# open-lux-A.net
KiCad netlist of a schematic drawn in EAGLE
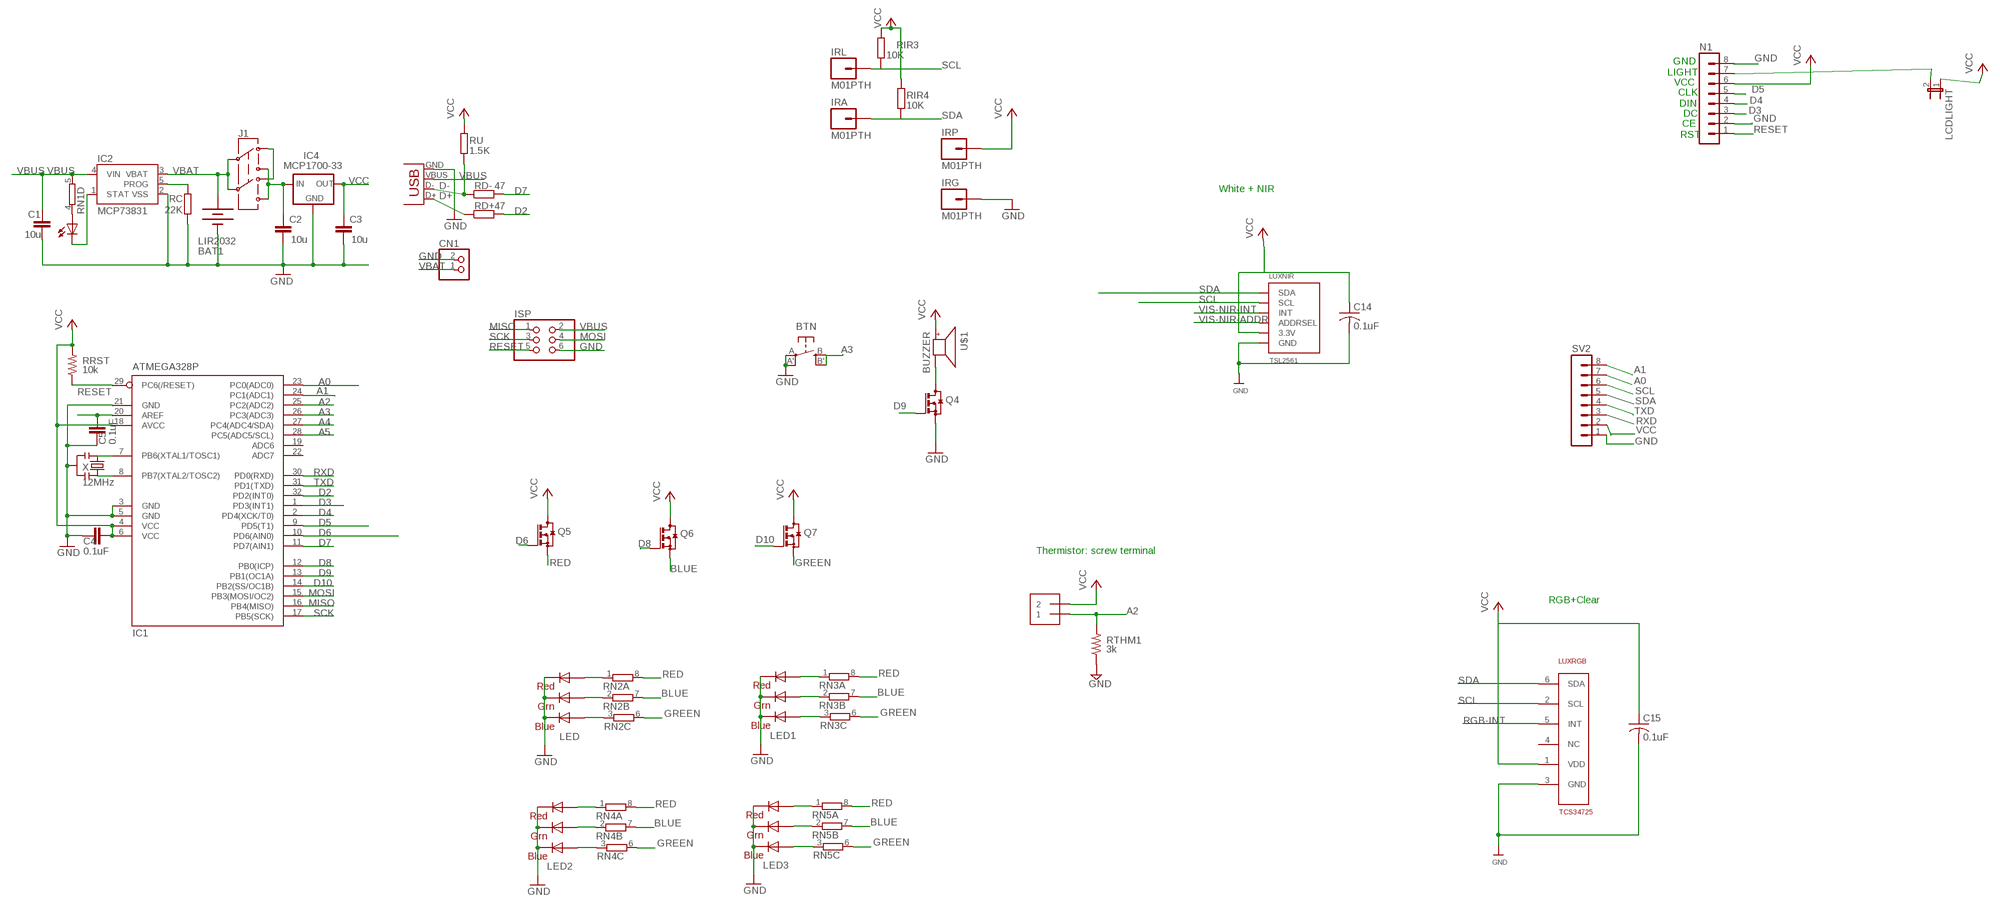
[diagram p0: schematic, sheet 1]

(export (version "E")
  (design (tool "Eeschema 10.0.6"))
  (components
    (comp (ref "BAT1")
      (value "LIR2032")
      (footprint "eagle-import:BATTCOM_20MM_PTH_SMT")
      (libsource (lib "eagle-import") (part "BATTERYBATTCOM_20MM_PTH_SMT"))
    )
    (comp (ref "BTN")
      (value "EVQQ2")
      (footprint "eagle-import:EVQ-Q2")
      (libsource (lib "eagle-import") (part "EVQQ2"))
    )
    (comp (ref "C1")
      (value "10u")
      (footprint "eagle-import:C0805")
      (libsource (lib "eagle-import") (part "resistor_C-EUC0805"))
    )
    (comp (ref "C2")
      (value "10u")
      (footprint "eagle-import:C0805")
      (libsource (lib "eagle-import") (part "resistor_C-EUC0805"))
    )
    (comp (ref "C3")
      (value "10u")
      (footprint "eagle-import:C0805")
      (libsource (lib "eagle-import") (part "resistor_C-EUC0805"))
    )
    (comp (ref "C4")
      (value "0.1uF")
      (footprint "eagle-import:C0805")
      (libsource (lib "eagle-import") (part "C-EUC0805"))
    )
    (comp (ref "C5")
      (value "0.1uF")
      (footprint "eagle-import:C0805")
      (libsource (lib "eagle-import") (part "C-EUC0805"))
    )
    (comp (ref "C14")
      (value "0.1uF")
      (footprint "eagle-import:C0805")
      (libsource (lib "eagle-import") (part "C-USC0805"))
    )
    (comp (ref "C15")
      (value "0.1uF")
      (footprint "eagle-import:C0805")
      (libsource (lib "eagle-import") (part "C-USC0805"))
    )
    (comp (ref "CHG")
      (value "0805")
      (footprint "eagle-import:CHIPLED_0805")
      (libsource (lib "eagle-import") (part "LEDCHIPLED_0805"))
    )
    (comp (ref "CN1")
      (value "JST_2PIN-SMT-RA")
      (footprint "eagle-import:JST-PH-2-SMT-RA")
      (libsource (lib "eagle-import") (part "JST_2PIN-SMT-RA"))
    )
    (comp (ref "IC1")
      (value "ATMEGA328P")
      (footprint "eagle-import:TQFP32-08")
      (fields (field (name "MPN") "ATMEGA8-16AU"))
      (libsource (lib "eagle-import") (part "MEGA8-AI"))
    )
    (comp (ref "IC2")
      (value "MCP73831")
      (footprint "eagle-import:SOT23-5")
      (libsource (lib "eagle-import") (part "MCP73831"))
    )
    (comp (ref "IC4")
      (value "MCP1700-33")
      (footprint "eagle-import:SOT23")
      (libsource (lib "eagle-import") (part "MCP1700SOT233"))
    )
    (comp (ref "IRA")
      (value "M01PTH")
      (footprint "eagle-import:1X01")
      (libsource (lib "eagle-import") (part "M01PTH"))
    )
    (comp (ref "IRG")
      (value "M01PTH")
      (footprint "eagle-import:1X01")
      (libsource (lib "eagle-import") (part "M01PTH"))
    )
    (comp (ref "IRL")
      (value "M01PTH")
      (footprint "eagle-import:1X01")
      (libsource (lib "eagle-import") (part "M01PTH"))
    )
    (comp (ref "IRP")
      (value "M01PTH")
      (footprint "eagle-import:1X01")
      (libsource (lib "eagle-import") (part "M01PTH"))
    )
    (comp (ref "ISP")
      (value "PINHD-2X3")
      (footprint "eagle-import:2X03")
      (libsource (lib "eagle-import") (part "PINHD-2X3"))
    )
    (comp (ref "J1")
      (value "AYZ0202")
      (footprint "eagle-import:AYZ0202")
      (libsource (lib "eagle-import") (part "AYZ0202"))
    )
    (comp (ref "LCDLIGHT")
      (value "JP1E")
      (footprint "eagle-import:JP1")
      (libsource (lib "eagle-import") (part "JP1E"))
    )
    (comp (ref "LED")
      (value "RGBLED5050")
      (footprint "eagle-import:RGBLED5050")
      (libsource (lib "eagle-import") (part "RGBLED5050"))
    )
    (comp (ref "LED1")
      (value "RGBLED5050")
      (footprint "eagle-import:RGBLED5050")
      (libsource (lib "eagle-import") (part "RGBLED5050"))
    )
    (comp (ref "LED2")
      (value "RGBLED5050")
      (footprint "eagle-import:RGBLED5050")
      (libsource (lib "eagle-import") (part "RGBLED5050"))
    )
    (comp (ref "LED3")
      (value "RGBLED5050")
      (footprint "eagle-import:RGBLED5050")
      (libsource (lib "eagle-import") (part "RGBLED5050"))
    )
    (comp (ref "LUXNIR")
      (value "TSL2561")
      (footprint "eagle-import:TSL2561_FN@1")
      (libsource (lib "eagle-import") (part "TSL2561"))
    )
    (comp (ref "LUXRGB")
      (value "TCS34725")
      (footprint "eagle-import:DFN-6")
      (libsource (lib "eagle-import") (part "TCS34725"))
    )
    (comp (ref "N1")
      (value "MA08-1")
      (footprint "eagle-import:MA08-1")
      (libsource (lib "eagle-import") (part "MA08-1"))
    )
    (comp (ref "Q4")
      (value "BSS123")
      (footprint "eagle-import:SOT23")
      (libsource (lib "eagle-import") (part "BSS123"))
    )
    (comp (ref "Q5")
      (value "BSS123")
      (footprint "eagle-import:SOT23")
      (libsource (lib "eagle-import") (part "BSS123"))
    )
    (comp (ref "Q6")
      (value "BSS123")
      (footprint "eagle-import:SOT23")
      (libsource (lib "eagle-import") (part "BSS123"))
    )
    (comp (ref "Q7")
      (value "BSS123")
      (footprint "eagle-import:SOT23")
      (libsource (lib "eagle-import") (part "BSS123"))
    )
    (comp (ref "RC")
      (value "22K")
      (footprint "eagle-import:R0805")
      (libsource (lib "eagle-import") (part "R-EU_R0805"))
    )
    (comp (ref "RD+")
      (value "47")
      (footprint "eagle-import:R0805")
      (libsource (lib "eagle-import") (part "R-EU_R0805"))
    )
    (comp (ref "RD-")
      (value "47")
      (footprint "eagle-import:R0805")
      (libsource (lib "eagle-import") (part "R-EU_R0805"))
    )
    (comp (ref "RIR3")
      (value "10K")
      (footprint "eagle-import:R0805")
      (libsource (lib "eagle-import") (part "R-EU_R0805"))
    )
    (comp (ref "RIR4")
      (value "10K")
      (footprint "eagle-import:R0805")
      (libsource (lib "eagle-import") (part "R-EU_R0805"))
    )
    (comp (ref "RN1")
      (value "4R-NEXB38V")
      (footprint "eagle-import:EXB38V")
      (libsource (lib "eagle-import") (part "4R-NEXB38V"))
    )
    (comp (ref "RN2")
      (value "4R-NEXB38V")
      (footprint "eagle-import:EXB38V")
      (libsource (lib "eagle-import") (part "4R-NEXB38V"))
    )
    (comp (ref "RN3")
      (value "4R-NEXB38V")
      (footprint "eagle-import:EXB38V")
      (libsource (lib "eagle-import") (part "4R-NEXB38V"))
    )
    (comp (ref "RN4")
      (value "4R-NEXB38V")
      (footprint "eagle-import:EXB38V")
      (libsource (lib "eagle-import") (part "4R-NEXB38V"))
    )
    (comp (ref "RN5")
      (value "4R-NEXB38V")
      (footprint "eagle-import:EXB38V")
      (libsource (lib "eagle-import") (part "4R-NEXB38V"))
    )
    (comp (ref "RRST")
      (value "10k")
      (footprint "eagle-import:R0805@1")
      (libsource (lib "eagle-import") (part "R-US_R0805"))
    )
    (comp (ref "RTHM1")
      (value "3k")
      (footprint "eagle-import:R0805@1")
      (libsource (lib "eagle-import") (part "R-US_R0805"))
    )
    (comp (ref "RU")
      (value "1.5K")
      (footprint "eagle-import:R0805")
      (libsource (lib "eagle-import") (part "R-EU_R0805"))
    )
    (comp (ref "SV2")
      (value "MA08-1")
      (footprint "eagle-import:MA08-1")
      (libsource (lib "eagle-import") (part "MA08-1"))
    )
    (comp (ref "THM1")
      (value "1X2-3.5MM")
      (footprint "eagle-import:1X2-3.5MM")
      (libsource (lib "eagle-import") (part "1X2-3.5MM"))
    )
    (comp (ref "U$1")
      (value "BUZZER")
      (footprint "eagle-import:SMT-8585-BUZZER")
      (libsource (lib "eagle-import") (part "BUZZER"))
    )
    (comp (ref "X")
      (value "12MHz")
      (footprint "eagle-import:RESONATOR-SMD")
      (libsource (lib "eagle-import") (part "RESONATORSMD"))
    )
    (comp (ref "X1")
      (value "USBSMD")
      (footprint "eagle-import:USB-MINIB")
      (libsource (lib "eagle-import") (part "USBSMD"))
    )
  )
  (nets
    (net (code "1") (name "/A0") (class "Default")
      (node (ref "IC1") (pin "23") (pinfunction "PC0(ADC0)_23") (pintype "bidirectional"))
      (node (ref "SV2") (pin "7") (pinfunction "7_7") (pintype "passive"))
    )
    (net (code "2") (name "/A1") (class "Default")
      (node (ref "IC1") (pin "24") (pinfunction "PC1(ADC1)_24") (pintype "bidirectional"))
      (node (ref "SV2") (pin "8") (pinfunction "8_8") (pintype "passive"))
    )
    (net (code "3") (name "/A2") (class "Default")
      (node (ref "IC1") (pin "25") (pinfunction "PC2(ADC2)_25") (pintype "bidirectional"))
      (node (ref "RTHM1") (pin "2") (pinfunction "2_2") (pintype "passive"))
      (node (ref "THM1") (pin "1") (pinfunction "1_1") (pintype "passive"))
    )
    (net (code "4") (name "/A3") (class "Default")
      (node (ref "BTN") (pin "B") (pinfunction "S_B") (pintype "passive"))
      (node (ref "BTN") (pin "B'") (pinfunction "S1_B'") (pintype "passive"))
      (node (ref "IC1") (pin "26") (pinfunction "PC3(ADC3)_26") (pintype "bidirectional"))
    )
    (net (code "5") (name "/A4") (class "Default")
      (node (ref "IC1") (pin "27") (pinfunction "PC4(ADC4/SDA)_27") (pintype "bidirectional"))
    )
    (net (code "6") (name "/A5") (class "Default")
      (node (ref "IC1") (pin "28") (pinfunction "PC5(ADC5/SCL)_28") (pintype "bidirectional"))
    )
    (net (code "7") (name "/BLUE") (class "Default")
      (node (ref "Q6") (pin "2") (pinfunction "S_2") (pintype "passive"))
      (node (ref "RN2") (pin "7") (pinfunction "2_7") (pintype "passive"))
      (node (ref "RN3") (pin "7") (pinfunction "2_7") (pintype "passive"))
      (node (ref "RN4") (pin "7") (pinfunction "2_7") (pintype "passive"))
      (node (ref "RN5") (pin "7") (pinfunction "2_7") (pintype "passive"))
    )
    (net (code "8") (name "/D+") (class "Default")
      (node (ref "RD+") (pin "1") (pinfunction "1_1") (pintype "passive"))
      (node (ref "X1") (pin "D+") (pinfunction "D+_D+") (pintype "bidirectional"))
    )
    (net (code "9") (name "/D-") (class "Default")
      (node (ref "RD-") (pin "1") (pinfunction "1_1") (pintype "passive"))
      (node (ref "RU") (pin "1") (pinfunction "1_1") (pintype "passive"))
      (node (ref "X1") (pin "D-") (pinfunction "D-_D-") (pintype "bidirectional"))
    )
    (net (code "10") (name "/D2") (class "Default")
      (node (ref "IC1") (pin "32") (pinfunction "PD2(INT0)_32") (pintype "bidirectional"))
      (node (ref "RD+") (pin "2") (pinfunction "2_2") (pintype "passive"))
    )
    (net (code "11") (name "/D3") (class "Default")
      (node (ref "IC1") (pin "1") (pinfunction "PD3(INT1)_1") (pintype "bidirectional"))
      (node (ref "N1") (pin "3") (pinfunction "3_3") (pintype "passive"))
    )
    (net (code "12") (name "/D4") (class "Default")
      (node (ref "IC1") (pin "2") (pinfunction "PD4(XCK/T0)_2") (pintype "bidirectional"))
      (node (ref "N1") (pin "4") (pinfunction "4_4") (pintype "passive"))
    )
    (net (code "13") (name "/D5") (class "Default")
      (node (ref "IC1") (pin "9") (pinfunction "PD5(T1)_9") (pintype "bidirectional"))
      (node (ref "N1") (pin "5") (pinfunction "5_5") (pintype "passive"))
    )
    (net (code "14") (name "/D6") (class "Default")
      (node (ref "IC1") (pin "10") (pinfunction "PD6(AIN0)_10") (pintype "bidirectional"))
      (node (ref "Q5") (pin "1") (pinfunction "G_1") (pintype "passive"))
    )
    (net (code "15") (name "/D7") (class "Default")
      (node (ref "IC1") (pin "11") (pinfunction "PD7(AIN1)_11") (pintype "bidirectional"))
      (node (ref "RD-") (pin "2") (pinfunction "2_2") (pintype "passive"))
    )
    (net (code "16") (name "/D8") (class "Default")
      (node (ref "IC1") (pin "12") (pinfunction "PB0(ICP)_12") (pintype "bidirectional"))
      (node (ref "Q6") (pin "1") (pinfunction "G_1") (pintype "passive"))
    )
    (net (code "17") (name "/D9") (class "Default")
      (node (ref "IC1") (pin "13") (pinfunction "PB1(OC1A)_13") (pintype "bidirectional"))
      (node (ref "Q4") (pin "1") (pinfunction "G_1") (pintype "passive"))
    )
    (net (code "18") (name "/D10") (class "Default")
      (node (ref "IC1") (pin "14") (pinfunction "PB2(SS/OC1B)_14") (pintype "bidirectional"))
      (node (ref "Q7") (pin "1") (pinfunction "G_1") (pintype "passive"))
    )
    (net (code "19") (name "/GREEN") (class "Default")
      (node (ref "Q7") (pin "2") (pinfunction "S_2") (pintype "passive"))
      (node (ref "RN2") (pin "6") (pinfunction "2_6") (pintype "passive"))
      (node (ref "RN3") (pin "6") (pinfunction "2_6") (pintype "passive"))
      (node (ref "RN4") (pin "6") (pinfunction "2_6") (pintype "passive"))
      (node (ref "RN5") (pin "6") (pinfunction "2_6") (pintype "passive"))
    )
    (net (code "20") (name "/MISO") (class "Default")
      (node (ref "IC1") (pin "16") (pinfunction "PB4(MISO)_16") (pintype "bidirectional"))
      (node (ref "ISP") (pin "1") (pinfunction "1_1") (pintype "passive"))
    )
    (net (code "21") (name "/MOSI") (class "Default")
      (node (ref "IC1") (pin "15") (pinfunction "PB3(MOSI/OC2)_15") (pintype "bidirectional"))
      (node (ref "ISP") (pin "4") (pinfunction "4_4") (pintype "passive"))
    )
    (net (code "22") (name "/RED") (class "Default")
      (node (ref "Q5") (pin "2") (pinfunction "S_2") (pintype "passive"))
      (node (ref "RN2") (pin "8") (pinfunction "2_8") (pintype "passive"))
      (node (ref "RN3") (pin "8") (pinfunction "2_8") (pintype "passive"))
      (node (ref "RN4") (pin "8") (pinfunction "2_8") (pintype "passive"))
      (node (ref "RN5") (pin "8") (pinfunction "2_8") (pintype "passive"))
    )
    (net (code "23") (name "/RESET") (class "Default")
      (node (ref "IC1") (pin "29") (pinfunction "PC6(/RESET)_29") (pintype "bidirectional"))
      (node (ref "ISP") (pin "5") (pinfunction "5_5") (pintype "passive"))
      (node (ref "N1") (pin "1") (pinfunction "1_1") (pintype "passive"))
      (node (ref "RRST") (pin "1") (pinfunction "1_1") (pintype "passive"))
    )
    (net (code "24") (name "/RGB-INT") (class "Default")
      (node (ref "LUXRGB") (pin "5") (pinfunction "INT_5") (pintype "bidirectional"))
    )
    (net (code "25") (name "/RXD") (class "Default")
      (node (ref "IC1") (pin "30") (pinfunction "PD0(RXD)_30") (pintype "bidirectional"))
      (node (ref "SV2") (pin "3") (pinfunction "3_3") (pintype "passive"))
    )
    (net (code "26") (name "/SCK") (class "Default")
      (node (ref "IC1") (pin "17") (pinfunction "PB5(SCK)_17") (pintype "bidirectional"))
      (node (ref "ISP") (pin "3") (pinfunction "3_3") (pintype "passive"))
    )
    (net (code "27") (name "/SCL") (class "Default")
      (node (ref "IRL") (pin "1") (pinfunction "1_1") (pintype "passive"))
      (node (ref "LUXNIR") (pin "CLK") (pinfunction "SCL_CLK") (pintype "bidirectional"))
      (node (ref "LUXRGB") (pin "2") (pinfunction "SCL_2") (pintype "bidirectional"))
      (node (ref "RIR3") (pin "1") (pinfunction "1_1") (pintype "passive"))
      (node (ref "SV2") (pin "6") (pinfunction "6_6") (pintype "passive"))
    )
    (net (code "28") (name "/SDA") (class "Default")
      (node (ref "IRA") (pin "1") (pinfunction "1_1") (pintype "passive"))
      (node (ref "LUXNIR") (pin "DATA") (pinfunction "SDA_DATA") (pintype "bidirectional"))
      (node (ref "LUXRGB") (pin "6") (pinfunction "SDA_6") (pintype "bidirectional"))
      (node (ref "RIR4") (pin "1") (pinfunction "1_1") (pintype "passive"))
      (node (ref "SV2") (pin "5") (pinfunction "5_5") (pintype "passive"))
    )
    (net (code "29") (name "/TXD") (class "Default")
      (node (ref "IC1") (pin "31") (pinfunction "PD1(TXD)_31") (pintype "bidirectional"))
      (node (ref "SV2") (pin "4") (pinfunction "4_4") (pintype "passive"))
    )
    (net (code "30") (name "/VBAT") (class "Default")
      (node (ref "BAT1") (pin "P$2") (pinfunction "+_P$2") (pintype "power_in"))
      (node (ref "CN1") (pin "1") (pinfunction "2_1") (pintype "passive"))
      (node (ref "IC2") (pin "3") (pinfunction "VBAT_3") (pintype "power_in"))
      (node (ref "J1") (pin "2") (pinfunction "2_2") (pintype "bidirectional"))
      (node (ref "J1") (pin "5") (pinfunction "5_5") (pintype "bidirectional"))
    )
    (net (code "31") (name "/VBUS") (class "Default")
      (node (ref "C1") (pin "1") (pinfunction "1_1") (pintype "passive"))
      (node (ref "IC2") (pin "4") (pinfunction "VIN_4") (pintype "power_in"))
      (node (ref "ISP") (pin "2") (pinfunction "2_2") (pintype "passive"))
      (node (ref "RN1") (pin "5") (pinfunction "2_5") (pintype "passive"))
      (node (ref "X1") (pin "VBUS") (pinfunction "VBUS_VBUS") (pintype "bidirectional"))
    )
    (net (code "32") (name "/VIS-NIR-ADDR") (class "Default")
      (node (ref "LUXNIR") (pin "ADR") (pinfunction "ADDRSEL_ADR") (pintype "bidirectional"))
    )
    (net (code "33") (name "/VIS-NIR-INT") (class "Default")
      (node (ref "LUXNIR") (pin "INT") (pinfunction "INT_INT") (pintype "bidirectional"))
    )
    (net (code "34") (name "GND") (class "Default")
      (node (ref "BAT1") (pin "P$1") (pinfunction "-_P$1") (pintype "power_in"))
      (node (ref "BTN") (pin "A") (pinfunction "P_A") (pintype "passive"))
      (node (ref "BTN") (pin "A'") (pinfunction "P1_A'") (pintype "passive"))
      (node (ref "C1") (pin "2") (pinfunction "2_2") (pintype "passive"))
      (node (ref "C14") (pin "2") (pinfunction "2_2") (pintype "passive"))
      (node (ref "C15") (pin "2") (pinfunction "2_2") (pintype "passive"))
      (node (ref "C2") (pin "2") (pinfunction "2_2") (pintype "passive"))
      (node (ref "C3") (pin "2") (pinfunction "2_2") (pintype "passive"))
      (node (ref "C4") (pin "1") (pinfunction "1_1") (pintype "passive"))
      (node (ref "C5") (pin "1") (pinfunction "1_1") (pintype "passive"))
      (node (ref "CN1") (pin "2") (pinfunction "1_2") (pintype "passive"))
      (node (ref "IC1") (pin "21") (pinfunction "GND_21") (pintype "power_in"))
      (node (ref "IC1") (pin "3") (pinfunction "GND_3") (pintype "power_in"))
      (node (ref "IC1") (pin "5") (pinfunction "GND_5") (pintype "power_in"))
      (node (ref "IC2") (pin "2") (pinfunction "VSS_2") (pintype "power_in"))
      (node (ref "IC4") (pin "1") (pinfunction "GND_1") (pintype "input"))
      (node (ref "IRG") (pin "1") (pinfunction "1_1") (pintype "passive"))
      (node (ref "ISP") (pin "6") (pinfunction "6_6") (pintype "passive"))
      (node (ref "LED") (pin "4") (pinfunction "BLUE_C_4") (pintype "bidirectional"))
      (node (ref "LED") (pin "5") (pinfunction "RED_C_5") (pintype "bidirectional"))
      (node (ref "LED") (pin "6") (pinfunction "GREEN_C_6") (pintype "bidirectional"))
      (node (ref "LED1") (pin "4") (pinfunction "BLUE_C_4") (pintype "bidirectional"))
      (node (ref "LED1") (pin "5") (pinfunction "RED_C_5") (pintype "bidirectional"))
      (node (ref "LED1") (pin "6") (pinfunction "GREEN_C_6") (pintype "bidirectional"))
      (node (ref "LED2") (pin "4") (pinfunction "BLUE_C_4") (pintype "bidirectional"))
      (node (ref "LED2") (pin "5") (pinfunction "RED_C_5") (pintype "bidirectional"))
      (node (ref "LED2") (pin "6") (pinfunction "GREEN_C_6") (pintype "bidirectional"))
      (node (ref "LED3") (pin "4") (pinfunction "BLUE_C_4") (pintype "bidirectional"))
      (node (ref "LED3") (pin "5") (pinfunction "RED_C_5") (pintype "bidirectional"))
      (node (ref "LED3") (pin "6") (pinfunction "GREEN_C_6") (pintype "bidirectional"))
      (node (ref "LUXNIR") (pin "VSS") (pinfunction "GND_VSS") (pintype "bidirectional"))
      (node (ref "LUXRGB") (pin "3") (pinfunction "GND_3") (pintype "bidirectional"))
      (node (ref "N1") (pin "2") (pinfunction "2_2") (pintype "passive"))
      (node (ref "N1") (pin "8") (pinfunction "8_8") (pintype "passive"))
      (node (ref "Q4") (pin "2") (pinfunction "S_2") (pintype "passive"))
      (node (ref "RC") (pin "1") (pinfunction "1_1") (pintype "passive"))
      (node (ref "RTHM1") (pin "1") (pinfunction "1_1") (pintype "passive"))
      (node (ref "SV2") (pin "1") (pinfunction "1_1") (pintype "passive"))
      (node (ref "X") (pin "2") (pinfunction "2_2") (pintype "passive"))
      (node (ref "X1") (pin "GND") (pinfunction "GND_GND") (pintype "bidirectional"))
    )
    (net (code "35") (name "Net-(IC1-AREF)") (class "Default")
      (node (ref "C5") (pin "2") (pinfunction "2_2") (pintype "passive"))
      (node (ref "IC1") (pin "20") (pinfunction "AREF_20") (pintype "passive"))
    )
    (net (code "36") (name "Net-(IC1-PB6(XTAL1{slash}TOSC1))") (class "Default")
      (node (ref "IC1") (pin "7") (pinfunction "PB6(XTAL1/TOSC1)_7") (pintype "bidirectional"))
      (node (ref "X") (pin "1") (pinfunction "1_1") (pintype "passive"))
    )
    (net (code "37") (name "Net-(IC1-PB7(XTAL2{slash}TOSC2))") (class "Default")
      (node (ref "IC1") (pin "8") (pinfunction "PB7(XTAL2/TOSC2)_8") (pintype "bidirectional"))
      (node (ref "X") (pin "3") (pinfunction "3_3") (pintype "passive"))
    )
    (net (code "38") (name "Net-(IC2-PROG)") (class "Default")
      (node (ref "IC2") (pin "5") (pinfunction "PROG_5") (pintype "input"))
      (node (ref "RC") (pin "2") (pinfunction "2_2") (pintype "passive"))
    )
    (net (code "39") (name "Net-(IC2-STAT)") (class "Default")
      (node (ref "CHG") (pin "C") (pinfunction "C_C") (pintype "passive"))
      (node (ref "IC2") (pin "1") (pinfunction "STAT_1") (pintype "output"))
    )
    (net (code "40") (name "Net-(IC4-IN)") (class "Default")
      (node (ref "C2") (pin "1") (pinfunction "1_1") (pintype "passive"))
      (node (ref "IC4") (pin "3") (pinfunction "IN_3") (pintype "input"))
      (node (ref "J1") (pin "1") (pinfunction "3_1") (pintype "bidirectional"))
      (node (ref "J1") (pin "4") (pinfunction "6_4") (pintype "bidirectional"))
    )
    (net (code "41") (name "Net-(J1-1)") (class "Default")
      (node (ref "J1") (pin "3") (pinfunction "1_3") (pintype "bidirectional"))
      (node (ref "J1") (pin "6") (pinfunction "4_6") (pintype "bidirectional"))
    )
    (net (code "42") (name "Net-(LCDLIGHT-Pad2)") (class "Default")
      (node (ref "LCDLIGHT") (pin "2") (pinfunction "2_2") (pintype "passive"))
      (node (ref "N1") (pin "7") (pinfunction "7_7") (pintype "passive"))
    )
    (net (code "43") (name "Net-(LED-BLUE_A)") (class "Default")
      (node (ref "LED") (pin "3") (pinfunction "BLUE_A_3") (pintype "bidirectional"))
      (node (ref "RN2") (pin "3") (pinfunction "1_3") (pintype "passive"))
    )
    (net (code "44") (name "Net-(LED-GREEN_A)") (class "Default")
      (node (ref "LED") (pin "1") (pinfunction "GREEN_A_1") (pintype "bidirectional"))
      (node (ref "RN2") (pin "2") (pinfunction "1_2") (pintype "passive"))
    )
    (net (code "45") (name "Net-(LED-RED_A)") (class "Default")
      (node (ref "LED") (pin "2") (pinfunction "RED_A_2") (pintype "bidirectional"))
      (node (ref "RN2") (pin "1") (pinfunction "1_1") (pintype "passive"))
    )
    (net (code "46") (name "Net-(LED1-BLUE_A)") (class "Default")
      (node (ref "LED1") (pin "3") (pinfunction "BLUE_A_3") (pintype "bidirectional"))
      (node (ref "RN3") (pin "3") (pinfunction "1_3") (pintype "passive"))
    )
    (net (code "47") (name "Net-(LED1-GREEN_A)") (class "Default")
      (node (ref "LED1") (pin "1") (pinfunction "GREEN_A_1") (pintype "bidirectional"))
      (node (ref "RN3") (pin "2") (pinfunction "1_2") (pintype "passive"))
    )
    (net (code "48") (name "Net-(LED1-RED_A)") (class "Default")
      (node (ref "LED1") (pin "2") (pinfunction "RED_A_2") (pintype "bidirectional"))
      (node (ref "RN3") (pin "1") (pinfunction "1_1") (pintype "passive"))
    )
    (net (code "49") (name "Net-(LED2-BLUE_A)") (class "Default")
      (node (ref "LED2") (pin "3") (pinfunction "BLUE_A_3") (pintype "bidirectional"))
      (node (ref "RN4") (pin "3") (pinfunction "1_3") (pintype "passive"))
    )
    (net (code "50") (name "Net-(LED2-GREEN_A)") (class "Default")
      (node (ref "LED2") (pin "1") (pinfunction "GREEN_A_1") (pintype "bidirectional"))
      (node (ref "RN4") (pin "2") (pinfunction "1_2") (pintype "passive"))
    )
    (net (code "51") (name "Net-(LED2-RED_A)") (class "Default")
      (node (ref "LED2") (pin "2") (pinfunction "RED_A_2") (pintype "bidirectional"))
      (node (ref "RN4") (pin "1") (pinfunction "1_1") (pintype "passive"))
    )
    (net (code "52") (name "Net-(LED3-BLUE_A)") (class "Default")
      (node (ref "LED3") (pin "3") (pinfunction "BLUE_A_3") (pintype "bidirectional"))
      (node (ref "RN5") (pin "3") (pinfunction "1_3") (pintype "passive"))
    )
    (net (code "53") (name "Net-(LED3-GREEN_A)") (class "Default")
      (node (ref "LED3") (pin "1") (pinfunction "GREEN_A_1") (pintype "bidirectional"))
      (node (ref "RN5") (pin "2") (pinfunction "1_2") (pintype "passive"))
    )
    (net (code "54") (name "Net-(LED3-RED_A)") (class "Default")
      (node (ref "LED3") (pin "2") (pinfunction "RED_A_2") (pintype "bidirectional"))
      (node (ref "RN5") (pin "1") (pinfunction "1_1") (pintype "passive"))
    )
    (net (code "55") (name "Net-(Q4-D)") (class "Default")
      (node (ref "Q4") (pin "3") (pinfunction "D_3") (pintype "passive"))
      (node (ref "U$1") (pin "-") (pinfunction "-_-") (pintype "passive"))
    )
    (net (code "56") (name "Net-(RN1D-1)") (class "Default")
      (node (ref "CHG") (pin "A") (pinfunction "A_A") (pintype "passive"))
      (node (ref "RN1") (pin "4") (pinfunction "1_4") (pintype "passive"))
    )
    (net (code "57") (name "VCC") (class "Default")
      (node (ref "C14") (pin "1") (pinfunction "1_1") (pintype "passive"))
      (node (ref "C15") (pin "1") (pinfunction "1_1") (pintype "passive"))
      (node (ref "C3") (pin "1") (pinfunction "1_1") (pintype "passive"))
      (node (ref "C4") (pin "2") (pinfunction "2_2") (pintype "passive"))
      (node (ref "IC1") (pin "18") (pinfunction "AVCC_18") (pintype "power_in"))
      (node (ref "IC1") (pin "4") (pinfunction "VCC_4") (pintype "power_in"))
      (node (ref "IC1") (pin "6") (pinfunction "VCC_6") (pintype "power_in"))
      (node (ref "IC4") (pin "2") (pinfunction "OUT_2") (pintype "passive"))
      (node (ref "IRP") (pin "1") (pinfunction "1_1") (pintype "passive"))
      (node (ref "LCDLIGHT") (pin "1") (pinfunction "1_1") (pintype "passive"))
      (node (ref "LUXNIR") (pin "VDD") (pinfunction "3.3V_VDD") (pintype "bidirectional"))
      (node (ref "LUXRGB") (pin "1") (pinfunction "VDD_1") (pintype "bidirectional"))
      (node (ref "N1") (pin "6") (pinfunction "6_6") (pintype "passive"))
      (node (ref "Q5") (pin "3") (pinfunction "D_3") (pintype "passive"))
      (node (ref "Q6") (pin "3") (pinfunction "D_3") (pintype "passive"))
      (node (ref "Q7") (pin "3") (pinfunction "D_3") (pintype "passive"))
      (node (ref "RIR3") (pin "2") (pinfunction "2_2") (pintype "passive"))
      (node (ref "RIR4") (pin "2") (pinfunction "2_2") (pintype "passive"))
      (node (ref "RRST") (pin "2") (pinfunction "2_2") (pintype "passive"))
      (node (ref "RU") (pin "2") (pinfunction "2_2") (pintype "passive"))
      (node (ref "SV2") (pin "2") (pinfunction "2_2") (pintype "passive"))
      (node (ref "THM1") (pin "2") (pinfunction "2_2") (pintype "passive"))
      (node (ref "U$1") (pin "+") (pinfunction "+_+") (pintype "passive"))
    )
    (net (code "58") (name "unconnected-(IC1-ADC6-Pad19)") (class "Default")
      (node (ref "IC1") (pin "19") (pinfunction "ADC6_19") (pintype "bidirectional"))
    )
    (net (code "59") (name "unconnected-(IC1-ADC7-Pad22)") (class "Default")
      (node (ref "IC1") (pin "22") (pinfunction "ADC7_22") (pintype "bidirectional"))
    )
    (net (code "60") (name "unconnected-(LUXRGB-NC-Pad4)") (class "Default")
      (node (ref "LUXRGB") (pin "4") (pinfunction "NC_4") (pintype "bidirectional"))
    )
  )
)
